# LR1121EVM.net
KiCad netlist of a schematic drawn in Altium Designer
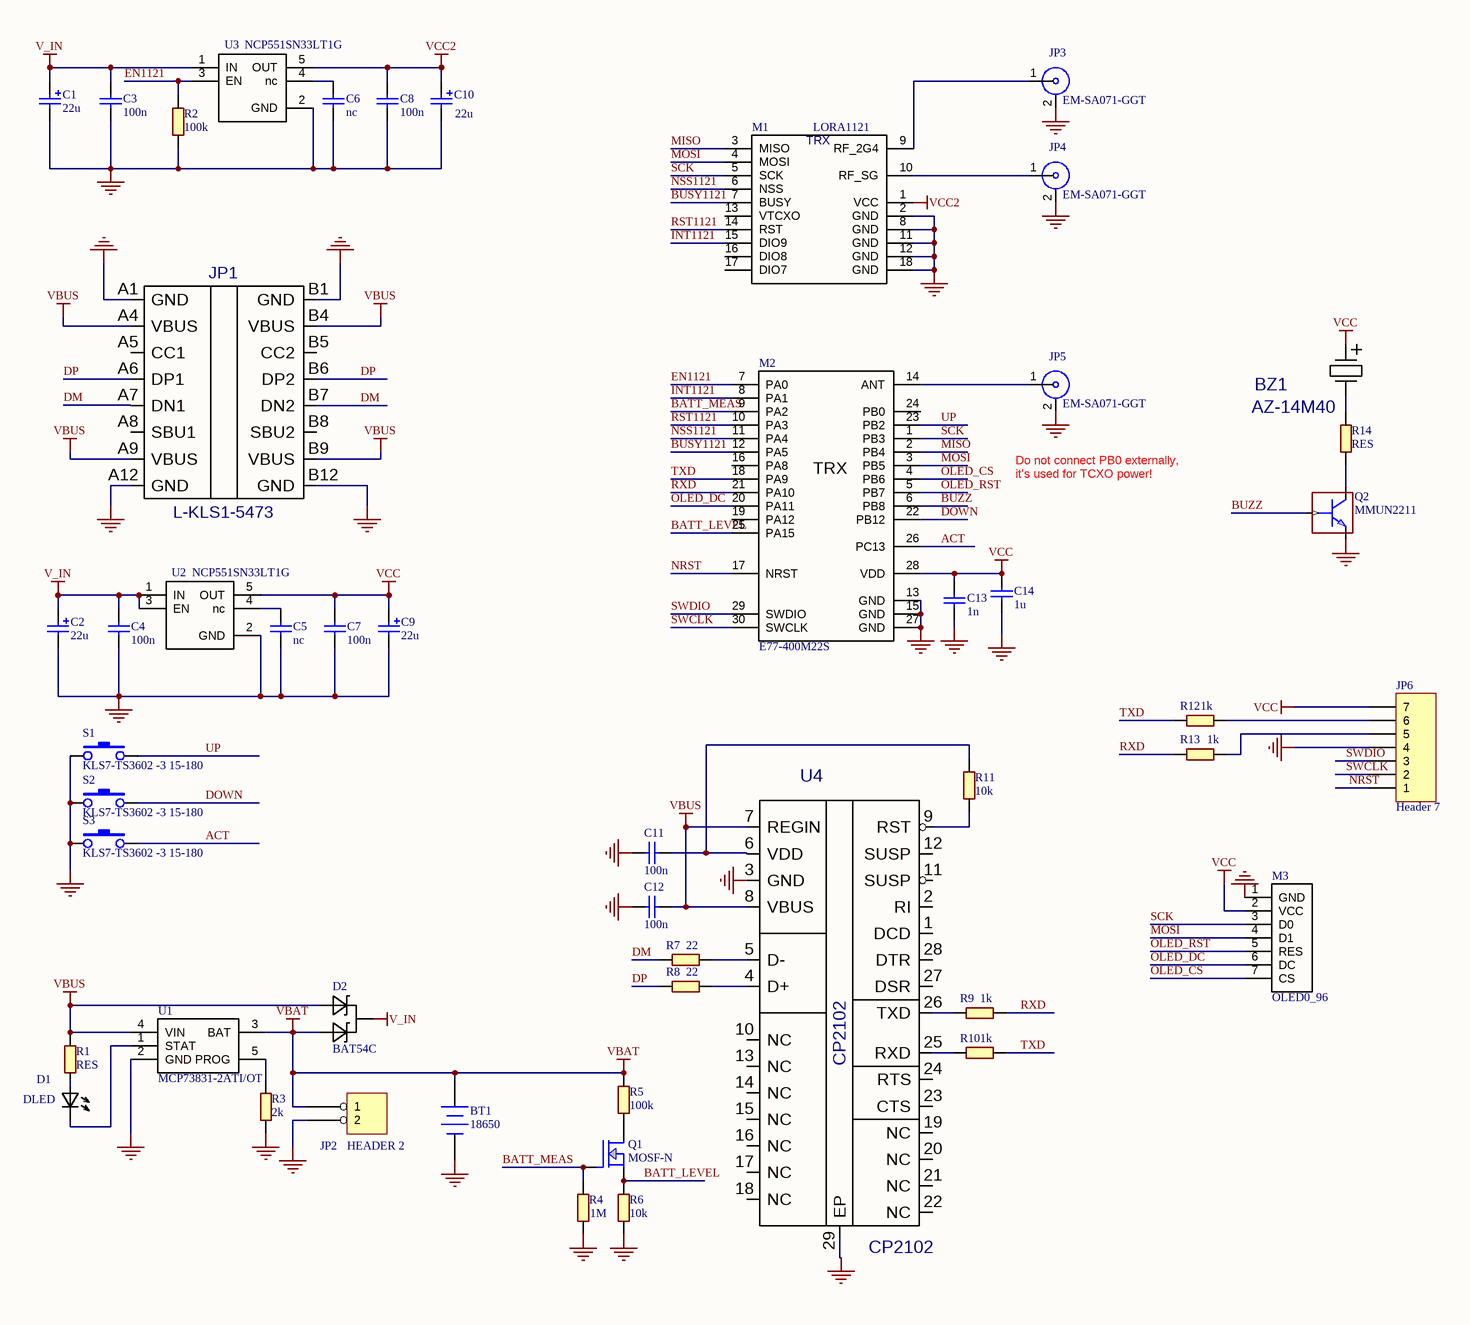
[diagram p0: LR1121EVM.SchDoc]

(export (version "E")
  (design (tool "Eeschema 10.0.6"))
  (components
    (comp (ref "BT1")
      (value "18650")
      (footprint "18650")
      (description "Multicell Battery")
      (fields (field (name "PUBLISHER") "Altium Limited"))
      (libsource (lib "zucker") (part "Battery"))
    )
    (comp (ref "BZ1")
      (value "AZ-14M40")
      (footprint "AZ-14M40")
      (libsource (lib "zucker") (part "BUZ-AZ-14M40"))
    )
    (comp (ref "C1")
      (value "22u")
      (footprint "C_TANTAL_A")
      (fields (field (name "VOLTAGE") "16V"))
      (libsource (lib "Passive") (part "CAPP"))
    )
    (comp (ref "C2")
      (value "22u")
      (footprint "C_TANTAL_A")
      (fields (field (name "VOLTAGE") "16V"))
      (libsource (lib "Passive") (part "CAPP"))
    )
    (comp (ref "C3")
      (value "100n")
      (footprint "C-0603")
      (fields (field (name "VOLTAGE") "50V"))
      (libsource (lib "Passive") (part "CAPN"))
    )
    (comp (ref "C4")
      (value "100n")
      (footprint "C-0603")
      (fields (field (name "VOLTAGE") "50V"))
      (libsource (lib "Passive") (part "CAPN"))
    )
    (comp (ref "C5")
      (value "nc")
      (footprint "C-0603")
      (fields (field (name "VOLTAGE") "50V"))
      (libsource (lib "Passive") (part "CAPN"))
    )
    (comp (ref "C6")
      (value "nc")
      (footprint "C-0603")
      (fields (field (name "VOLTAGE") "50V"))
      (libsource (lib "Passive") (part "CAPN"))
    )
    (comp (ref "C7")
      (value "100n")
      (footprint "C-0603")
      (fields (field (name "VOLTAGE") "50V"))
      (libsource (lib "Passive") (part "CAPN"))
    )
    (comp (ref "C8")
      (value "100n")
      (footprint "C-0603")
      (fields (field (name "VOLTAGE") "50V"))
      (libsource (lib "Passive") (part "CAPN"))
    )
    (comp (ref "C9")
      (value "22u")
      (footprint "C_TANTAL_A")
      (fields (field (name "VOLTAGE") "16V"))
      (libsource (lib "Passive") (part "CAPP"))
    )
    (comp (ref "C10")
      (value "22u")
      (footprint "C_TANTAL_A")
      (fields (field (name "VOLTAGE") "16V"))
      (libsource (lib "Passive") (part "CAPP"))
    )
    (comp (ref "C11")
      (value "100n")
      (footprint "C-0603")
      (fields (field (name "VOLTAGE") "50V"))
      (libsource (lib "Passive") (part "CAPN"))
    )
    (comp (ref "C12")
      (value "100n")
      (footprint "C-0603")
      (fields (field (name "VOLTAGE") "50V"))
      (libsource (lib "Passive") (part "CAPN"))
    )
    (comp (ref "C13")
      (value "1n")
      (footprint "C-0603")
      (fields (field (name "VOLTAGE") "50V"))
      (libsource (lib "Passive") (part "CAPN"))
    )
    (comp (ref "C14")
      (value "1u")
      (footprint "C-0603")
      (fields (field (name "VOLTAGE") "50V"))
      (libsource (lib "Passive") (part "CAPN"))
    )
    (comp (ref "D1") (value "DLED") (footprint "LED_3mm_RED") (libsource (lib "zucker") (part "DLED")))
    (comp (ref "D2") (value "BAT54C") (footprint "SOT-23") (libsource (lib "zucker") (part "BAT54C")))
    (comp (ref "JP1")
      (value "L-KLS1-5473")
      (footprint "L-KLS1-5473")
      (libsource (lib "connectors") (part "L-KLS1-5473"))
    )
    (comp (ref "JP2")
      (value "HEADER 2")
      (footprint "PLS1-2")
      (libsource (lib "Connectors") (part "HEADER 2"))
    )
    (comp (ref "JP3")
      (value "EM-SA071-GGT")
      (footprint "SMA_F_EDGE")
      (description "SMA Female R/A PCB Mount")
      (libsource (lib "Connectors") (part "SMA"))
    )
    (comp (ref "JP4")
      (value "EM-SA071-GGT")
      (footprint "SMA_F_EDGE")
      (description "SMA Female R/A PCB Mount")
      (libsource (lib "Connectors") (part "SMA"))
    )
    (comp (ref "JP5")
      (value "EM-SA071-GGT")
      (footprint "SMA_F_EDGE")
      (description "SMA Female R/A PCB Mount")
      (libsource (lib "Connectors") (part "SMA"))
    )
    (comp (ref "JP6")
      (value "Header 7")
      (footprint "PLS1-7R")
      (description "Header, 7-Pin")
      (fields (field (name "PUBLISHER") "Altium Limited"))
      (libsource (lib "Miscellaneous Connectors") (part "Header 7"))
    )
    (comp (ref "M1")
      (value "LORA1121")
      (footprint "LORA1121")
      (libsource (lib "LR1121EVM") (part "LORA1121"))
    )
    (comp (ref "M2")
      (value "E77-400M22S")
      (footprint "E77XX-M22")
      (libsource (lib "zucker") (part "E77-400M22S"))
    )
    (comp (ref "M3") (value "OLED0_96") (footprint "OLED096") (libsource (lib "zucker") (part "OLED0_96")))
    (comp (ref "Q1") (value "MOSF-N") (footprint "SOT-23") (libsource (lib "Transistors") (part "MOSF-N")))
    (comp (ref "Q2")
      (value "MMUN2211")
      (footprint "SOT-23")
      (libsource (lib "Transistors") (part "MMUN2211"))
    )
    (comp (ref "R1") (value "RES") (footprint "R-0603") (libsource (lib "Passive") (part "RES")))
    (comp (ref "R2") (value "100k") (footprint "R-0603") (libsource (lib "Passive") (part "RES")))
    (comp (ref "R3") (value "2k") (footprint "R-0603") (libsource (lib "") (part "RES_2")))
    (comp (ref "R4") (value "1M") (footprint "R-0603") (libsource (lib "Passive") (part "RES")))
    (comp (ref "R5") (value "100k") (footprint "R-0603") (libsource (lib "Passive") (part "RES")))
    (comp (ref "R6") (value "10k") (footprint "R-0603") (libsource (lib "Passive") (part "RES")))
    (comp (ref "R7") (value "22") (footprint "R-0603") (libsource (lib "") (part "RES_1")))
    (comp (ref "R8") (value "22") (footprint "R-0603") (libsource (lib "") (part "RES_1")))
    (comp (ref "R9") (value "1k") (footprint "R-0603") (libsource (lib "") (part "RES_1")))
    (comp (ref "R10") (value "1k") (footprint "R-0603") (libsource (lib "") (part "RES_1")))
    (comp (ref "R11") (value "10k") (footprint "R-0603") (libsource (lib "Passive") (part "RES")))
    (comp (ref "R12") (value "1k") (footprint "R-0603") (libsource (lib "") (part "RES_1")))
    (comp (ref "R13") (value "1k") (footprint "R-0603") (libsource (lib "") (part "RES_1")))
    (comp (ref "R14") (value "RES") (footprint "R-0603") (libsource (lib "Passive") (part "RES")))
    (comp (ref "S1")
      (value "KLS7-TS3602 -3 15-180")
      (footprint "KLS7-TS3602")
      (libsource (lib "Switches") (part "SW-1"))
    )
    (comp (ref "S2")
      (value "KLS7-TS3602 -3 15-180")
      (footprint "KLS7-TS3602")
      (libsource (lib "Switches") (part "SW-1"))
    )
    (comp (ref "S3")
      (value "KLS7-TS3602 -3 15-180")
      (footprint "KLS7-TS3602")
      (libsource (lib "Switches") (part "SW-1"))
    )
    (comp (ref "U1")
      (value "MCP73831-2ATI/OT")
      (footprint "SOT-23-5")
      (libsource (lib "zucker") (part "MCP73831"))
    )
    (comp (ref "U2")
      (value "NCP551SN33LT1G")
      (footprint "SOT-23-5")
      (description "50mA Low-Dropout Regulator")
      (libsource (lib "zucker") (part "LP2980"))
    )
    (comp (ref "U3")
      (value "NCP551SN33LT1G")
      (footprint "SOT-23-5")
      (description "50mA Low-Dropout Regulator")
      (libsource (lib "zucker") (part "LP2980"))
    )
    (comp (ref "U4") (value "CP2102") (footprint "QFN28") (libsource (lib "E2002") (part "CP2102")))
  )
  (nets
    (net (code "1") (name "/ACT") (class "Default")
      (node (ref "M2") (pin "26") (pinfunction "PC13_26") (pintype "passive"))
      (node (ref "S3") (pin "2") (pinfunction "2_2") (pintype "passive"))
    )
    (net (code "2") (name "/BATT_LEVEL") (class "Default")
      (node (ref "M2") (pin "25") (pinfunction "PA15_25") (pintype "passive"))
      (node (ref "Q1") (pin "2") (pinfunction "SOURCE_2") (pintype "passive"))
      (node (ref "R6") (pin "1") (pinfunction "1_1") (pintype "passive"))
    )
    (net (code "3") (name "/BATT_MEAS") (class "Default")
      (node (ref "M2") (pin "9") (pinfunction "PA2_9") (pintype "passive"))
      (node (ref "Q1") (pin "1") (pinfunction "GATE_1") (pintype "passive"))
      (node (ref "R4") (pin "1") (pinfunction "1_1") (pintype "passive"))
    )
    (net (code "4") (name "/BUSY1121") (class "Default")
      (node (ref "M1") (pin "7") (pinfunction "BUSY_7") (pintype "passive"))
      (node (ref "M2") (pin "12") (pinfunction "PA5_12") (pintype "passive"))
    )
    (net (code "5") (name "/BUZZ") (class "Default")
      (node (ref "M2") (pin "6") (pinfunction "PB8_6") (pintype "passive"))
      (node (ref "Q2") (pin "1") (pinfunction "BASE_1") (pintype "input"))
    )
    (net (code "6") (name "/DM") (class "Default")
      (node (ref "JP1") (pin "A7") (pinfunction "DN1_A7") (pintype "passive"))
      (node (ref "JP1") (pin "B7") (pinfunction "DN2_B7") (pintype "passive"))
      (node (ref "R7") (pin "2") (pinfunction "2_2") (pintype "passive"))
    )
    (net (code "7") (name "/DOWN") (class "Default")
      (node (ref "M2") (pin "22") (pinfunction "PB12_22") (pintype "passive"))
      (node (ref "S2") (pin "2") (pinfunction "2_2") (pintype "passive"))
    )
    (net (code "8") (name "/DP") (class "Default")
      (node (ref "JP1") (pin "A6") (pinfunction "DP1_A6") (pintype "passive"))
      (node (ref "JP1") (pin "B6") (pinfunction "DP2_B6") (pintype "passive"))
      (node (ref "R8") (pin "2") (pinfunction "2_2") (pintype "passive"))
    )
    (net (code "9") (name "/EN1121") (class "Default")
      (node (ref "M2") (pin "7") (pinfunction "PA0_7") (pintype "passive"))
      (node (ref "R2") (pin "1") (pinfunction "1_1") (pintype "passive"))
      (node (ref "U3") (pin "3") (pinfunction "EN_3") (pintype "passive"))
    )
    (net (code "10") (name "/INT1121") (class "Default")
      (node (ref "M1") (pin "15") (pinfunction "DIO9_15") (pintype "passive"))
      (node (ref "M2") (pin "8") (pinfunction "PA1_8") (pintype "passive"))
    )
    (net (code "11") (name "/MISO") (class "Default")
      (node (ref "M1") (pin "3") (pinfunction "MISO_3") (pintype "passive"))
      (node (ref "M2") (pin "2") (pinfunction "PB4_2") (pintype "passive"))
    )
    (net (code "12") (name "/MOSI") (class "Default")
      (node (ref "M1") (pin "4") (pinfunction "MOSI_4") (pintype "passive"))
      (node (ref "M2") (pin "3") (pinfunction "PB5_3") (pintype "passive"))
      (node (ref "M3") (pin "4") (pinfunction "D1_4") (pintype "passive"))
    )
    (net (code "13") (name "/NRST") (class "Default")
      (node (ref "JP6") (pin "1") (pinfunction "1_1") (pintype "passive"))
      (node (ref "M2") (pin "17") (pinfunction "NRST_17") (pintype "passive"))
    )
    (net (code "14") (name "/NSS1121") (class "Default")
      (node (ref "M1") (pin "6") (pinfunction "NSS_6") (pintype "passive"))
      (node (ref "M2") (pin "11") (pinfunction "PA4_11") (pintype "passive"))
    )
    (net (code "15") (name "/OLED_CS") (class "Default")
      (node (ref "M2") (pin "4") (pinfunction "PB6_4") (pintype "passive"))
      (node (ref "M3") (pin "7") (pinfunction "CS_7") (pintype "passive"))
    )
    (net (code "16") (name "/OLED_DC") (class "Default")
      (node (ref "M2") (pin "20") (pinfunction "PA11_20") (pintype "passive"))
      (node (ref "M3") (pin "6") (pinfunction "DC_6") (pintype "passive"))
    )
    (net (code "17") (name "/OLED_RST") (class "Default")
      (node (ref "M2") (pin "5") (pinfunction "PB7_5") (pintype "passive"))
      (node (ref "M3") (pin "5") (pinfunction "RES_5") (pintype "passive"))
    )
    (net (code "18") (name "/RST1121") (class "Default")
      (node (ref "M1") (pin "14") (pinfunction "RST_14") (pintype "passive"))
      (node (ref "M2") (pin "10") (pinfunction "PA3_10") (pintype "passive"))
    )
    (net (code "19") (name "/RXD") (class "Default")
      (node (ref "M2") (pin "21") (pinfunction "PA10_21") (pintype "passive"))
      (node (ref "R13") (pin "2") (pinfunction "2_2") (pintype "passive"))
      (node (ref "R9") (pin "1") (pinfunction "1_1") (pintype "passive"))
    )
    (net (code "20") (name "/SCK") (class "Default")
      (node (ref "M1") (pin "5") (pinfunction "SCK_5") (pintype "passive"))
      (node (ref "M2") (pin "1") (pinfunction "PB3_1") (pintype "passive"))
      (node (ref "M3") (pin "3") (pinfunction "D0_3") (pintype "passive"))
    )
    (net (code "21") (name "/SWCLK") (class "Default")
      (node (ref "JP6") (pin "2") (pinfunction "2_2") (pintype "passive"))
      (node (ref "M2") (pin "30") (pinfunction "SWCLK_30") (pintype "passive"))
    )
    (net (code "22") (name "/SWDIO") (class "Default")
      (node (ref "JP6") (pin "3") (pinfunction "3_3") (pintype "passive"))
      (node (ref "M2") (pin "29") (pinfunction "SWDIO_29") (pintype "passive"))
    )
    (net (code "23") (name "/TXD") (class "Default")
      (node (ref "M2") (pin "18") (pinfunction "PA9_18") (pintype "passive"))
      (node (ref "R10") (pin "1") (pinfunction "1_1") (pintype "passive"))
      (node (ref "R12") (pin "2") (pinfunction "2_2") (pintype "passive"))
    )
    (net (code "24") (name "/UP") (class "Default")
      (node (ref "M2") (pin "23") (pinfunction "PB2_23") (pintype "passive"))
      (node (ref "S1") (pin "2") (pinfunction "2_2") (pintype "passive"))
    )
    (net (code "25") (name "GND") (class "Default")
      (node (ref "BT1") (pin "2") (pinfunction "-_2") (pintype "passive"))
      (node (ref "C1") (pin "1") (pinfunction "1_1") (pintype "passive"))
      (node (ref "C10") (pin "1") (pinfunction "1_1") (pintype "passive"))
      (node (ref "C11") (pin "2") (pinfunction "2_2") (pintype "passive"))
      (node (ref "C12") (pin "1") (pinfunction "1_1") (pintype "passive"))
      (node (ref "C13") (pin "2") (pinfunction "2_2") (pintype "passive"))
      (node (ref "C14") (pin "2") (pinfunction "2_2") (pintype "passive"))
      (node (ref "C2") (pin "1") (pinfunction "1_1") (pintype "passive"))
      (node (ref "C3") (pin "2") (pinfunction "2_2") (pintype "passive"))
      (node (ref "C4") (pin "2") (pinfunction "2_2") (pintype "passive"))
      (node (ref "C5") (pin "2") (pinfunction "2_2") (pintype "passive"))
      (node (ref "C6") (pin "2") (pinfunction "2_2") (pintype "passive"))
      (node (ref "C7") (pin "2") (pinfunction "2_2") (pintype "passive"))
      (node (ref "C8") (pin "2") (pinfunction "2_2") (pintype "passive"))
      (node (ref "C9") (pin "1") (pinfunction "1_1") (pintype "passive"))
      (node (ref "JP1") (pin "A1") (pinfunction "GND_A1") (pintype "passive"))
      (node (ref "JP1") (pin "A12") (pinfunction "GND_A12") (pintype "passive"))
      (node (ref "JP1") (pin "B1") (pinfunction "GND_B1") (pintype "passive"))
      (node (ref "JP1") (pin "B12") (pinfunction "GND_B12") (pintype "passive"))
      (node (ref "JP2") (pin "2") (pinfunction "2_2") (pintype "passive"))
      (node (ref "JP3") (pin "2") (pinfunction "2_2") (pintype "passive"))
      (node (ref "JP4") (pin "2") (pinfunction "2_2") (pintype "passive"))
      (node (ref "JP5") (pin "2") (pinfunction "2_2") (pintype "passive"))
      (node (ref "JP6") (pin "4") (pinfunction "4_4") (pintype "passive"))
      (node (ref "M1") (pin "11") (pinfunction "GND_11") (pintype "passive"))
      (node (ref "M1") (pin "12") (pinfunction "GND_12") (pintype "passive"))
      (node (ref "M1") (pin "18") (pinfunction "GND_18") (pintype "passive"))
      (node (ref "M1") (pin "2") (pinfunction "GND_2") (pintype "passive"))
      (node (ref "M1") (pin "8") (pinfunction "GND_8") (pintype "passive"))
      (node (ref "M2") (pin "13") (pinfunction "GND_13") (pintype "passive"))
      (node (ref "M2") (pin "15") (pinfunction "GND_15") (pintype "passive"))
      (node (ref "M2") (pin "27") (pinfunction "GND_27") (pintype "passive"))
      (node (ref "M3") (pin "1") (pinfunction "GND_1") (pintype "passive"))
      (node (ref "Q2") (pin "2") (pinfunction "EMITTER_2") (pintype "passive"))
      (node (ref "R2") (pin "2") (pinfunction "2_2") (pintype "passive"))
      (node (ref "R3") (pin "1") (pinfunction "1_1") (pintype "passive"))
      (node (ref "R4") (pin "2") (pinfunction "2_2") (pintype "passive"))
      (node (ref "R6") (pin "2") (pinfunction "2_2") (pintype "passive"))
      (node (ref "S1") (pin "1") (pinfunction "1_1") (pintype "passive"))
      (node (ref "S2") (pin "1") (pinfunction "1_1") (pintype "passive"))
      (node (ref "S3") (pin "1") (pinfunction "1_1") (pintype "passive"))
      (node (ref "U1") (pin "2") (pinfunction "GND_2") (pintype "passive"))
      (node (ref "U2") (pin "2") (pinfunction "GND_2") (pintype "passive"))
      (node (ref "U3") (pin "2") (pinfunction "GND_2") (pintype "passive"))
      (node (ref "U4") (pin "29") (pinfunction "EP_29") (pintype "passive"))
      (node (ref "U4") (pin "3") (pinfunction "GND_3") (pintype "passive"))
    )
    (net (code "26") (name "Net-(BZ1-Pad2)") (class "Default")
      (node (ref "BZ1") (pin "2") (pinfunction "2_2") (pintype "passive"))
      (node (ref "R14") (pin "1") (pinfunction "1_1") (pintype "passive"))
    )
    (net (code "27") (name "Net-(D1-Pad1)") (class "Default")
      (node (ref "D1") (pin "1") (pinfunction "1_1") (pintype "passive"))
      (node (ref "R1") (pin "2") (pinfunction "2_2") (pintype "passive"))
    )
    (net (code "28") (name "Net-(JP6-Pad5)") (class "Default")
      (node (ref "JP6") (pin "5") (pinfunction "5_5") (pintype "passive"))
      (node (ref "R13") (pin "1") (pinfunction "1_1") (pintype "passive"))
    )
    (net (code "29") (name "Net-(JP6-Pad6)") (class "Default")
      (node (ref "JP6") (pin "6") (pinfunction "6_6") (pintype "passive"))
      (node (ref "R12") (pin "1") (pinfunction "1_1") (pintype "passive"))
    )
    (net (code "30") (name "Net-(M1-RF_2G4)") (class "Default")
      (node (ref "JP3") (pin "1") (pinfunction "1_1") (pintype "passive"))
      (node (ref "M1") (pin "9") (pinfunction "RF_2G4_9") (pintype "passive"))
    )
    (net (code "31") (name "Net-(M1-RF_SG)") (class "Default")
      (node (ref "JP4") (pin "1") (pinfunction "1_1") (pintype "passive"))
      (node (ref "M1") (pin "10") (pinfunction "RF_SG_10") (pintype "passive"))
    )
    (net (code "32") (name "Net-(M2-ANT)") (class "Default")
      (node (ref "JP5") (pin "1") (pinfunction "1_1") (pintype "passive"))
      (node (ref "M2") (pin "14") (pinfunction "ANT_14") (pintype "passive"))
    )
    (net (code "33") (name "Net-(Q1-DRAIN)") (class "Default")
      (node (ref "Q1") (pin "3") (pinfunction "DRAIN_3") (pintype "passive"))
      (node (ref "R5") (pin "2") (pinfunction "2_2") (pintype "passive"))
    )
    (net (code "34") (name "Net-(Q2-COLLECTOR)") (class "Default")
      (node (ref "Q2") (pin "3") (pinfunction "COLLECTOR_3") (pintype "passive"))
      (node (ref "R14") (pin "2") (pinfunction "2_2") (pintype "passive"))
    )
    (net (code "35") (name "Net-(U1-PROG)") (class "Default")
      (node (ref "R3") (pin "2") (pinfunction "2_2") (pintype "passive"))
      (node (ref "U1") (pin "5") (pinfunction "PROG_5") (pintype "passive"))
    )
    (net (code "36") (name "Net-(U1-STAT)") (class "Default")
      (node (ref "D1") (pin "2") (pinfunction "2_2") (pintype "passive"))
      (node (ref "U1") (pin "1") (pinfunction "STAT_1") (pintype "passive"))
    )
    (net (code "37") (name "Net-(U2-nc)") (class "Default")
      (node (ref "C5") (pin "1") (pinfunction "1_1") (pintype "passive"))
      (node (ref "U2") (pin "4") (pinfunction "nc_4") (pintype "passive"))
    )
    (net (code "38") (name "Net-(U3-nc)") (class "Default")
      (node (ref "C6") (pin "1") (pinfunction "1_1") (pintype "passive"))
      (node (ref "U3") (pin "4") (pinfunction "nc_4") (pintype "passive"))
    )
    (net (code "39") (name "Net-(U4-D+)") (class "Default")
      (node (ref "R8") (pin "1") (pinfunction "1_1") (pintype "passive"))
      (node (ref "U4") (pin "4") (pinfunction "D+_4") (pintype "passive"))
    )
    (net (code "40") (name "Net-(U4-D-)") (class "Default")
      (node (ref "R7") (pin "1") (pinfunction "1_1") (pintype "passive"))
      (node (ref "U4") (pin "5") (pinfunction "D-_5") (pintype "passive"))
    )
    (net (code "41") (name "Net-(U4-RST)") (class "Default")
      (node (ref "R11") (pin "2") (pinfunction "2_2") (pintype "passive"))
      (node (ref "U4") (pin "9") (pinfunction "RST_9") (pintype "passive"))
    )
    (net (code "42") (name "Net-(U4-RXD)") (class "Default")
      (node (ref "R10") (pin "2") (pinfunction "2_2") (pintype "passive"))
      (node (ref "U4") (pin "25") (pinfunction "RXD_25") (pintype "passive"))
    )
    (net (code "43") (name "Net-(U4-TXD)") (class "Default")
      (node (ref "R9") (pin "2") (pinfunction "2_2") (pintype "passive"))
      (node (ref "U4") (pin "26") (pinfunction "TXD_26") (pintype "passive"))
    )
    (net (code "44") (name "Net-(U4-VDD)") (class "Default")
      (node (ref "C11") (pin "1") (pinfunction "1_1") (pintype "passive"))
      (node (ref "R11") (pin "1") (pinfunction "1_1") (pintype "passive"))
      (node (ref "U4") (pin "6") (pinfunction "VDD_6") (pintype "passive"))
    )
    (net (code "45") (name "VBAT") (class "Default")
      (node (ref "BT1") (pin "1") (pinfunction "+_1") (pintype "passive"))
      (node (ref "D2") (pin "1") (pinfunction "A1_1") (pintype "passive"))
      (node (ref "JP2") (pin "1") (pinfunction "1_1") (pintype "passive"))
      (node (ref "R5") (pin "1") (pinfunction "1_1") (pintype "passive"))
      (node (ref "U1") (pin "3") (pinfunction "BAT_3") (pintype "passive"))
    )
    (net (code "46") (name "VBUS") (class "Default")
      (node (ref "C12") (pin "2") (pinfunction "2_2") (pintype "passive"))
      (node (ref "D2") (pin "2") (pinfunction "A2_2") (pintype "passive"))
      (node (ref "JP1") (pin "A4") (pinfunction "VBUS_A4") (pintype "passive"))
      (node (ref "JP1") (pin "A9") (pinfunction "VBUS_A9") (pintype "passive"))
      (node (ref "JP1") (pin "B4") (pinfunction "VBUS_B4") (pintype "passive"))
      (node (ref "JP1") (pin "B9") (pinfunction "VBUS_B9") (pintype "passive"))
      (node (ref "R1") (pin "1") (pinfunction "1_1") (pintype "passive"))
      (node (ref "U1") (pin "4") (pinfunction "VIN_4") (pintype "passive"))
      (node (ref "U4") (pin "7") (pinfunction "REGIN_7") (pintype "passive"))
      (node (ref "U4") (pin "8") (pinfunction "VBUS_8") (pintype "passive"))
    )
    (net (code "47") (name "VCC") (class "Default")
      (node (ref "BZ1") (pin "1") (pinfunction "1_1") (pintype "passive"))
      (node (ref "C13") (pin "1") (pinfunction "1_1") (pintype "passive"))
      (node (ref "C14") (pin "1") (pinfunction "1_1") (pintype "passive"))
      (node (ref "C7") (pin "1") (pinfunction "1_1") (pintype "passive"))
      (node (ref "C9") (pin "2") (pinfunction "2_2") (pintype "passive"))
      (node (ref "JP6") (pin "7") (pinfunction "7_7") (pintype "passive"))
      (node (ref "M2") (pin "28") (pinfunction "VDD_28") (pintype "passive"))
      (node (ref "M3") (pin "2") (pinfunction "VCC_2") (pintype "passive"))
      (node (ref "U2") (pin "5") (pinfunction "OUT_5") (pintype "passive"))
    )
    (net (code "48") (name "VCC2") (class "Default")
      (node (ref "C10") (pin "2") (pinfunction "2_2") (pintype "passive"))
      (node (ref "C8") (pin "1") (pinfunction "1_1") (pintype "passive"))
      (node (ref "M1") (pin "1") (pinfunction "VCC_1") (pintype "passive"))
      (node (ref "U3") (pin "5") (pinfunction "OUT_5") (pintype "passive"))
    )
    (net (code "49") (name "VSS") (class "Default")
      (node (ref "JP1") (pin "17") (pinfunction "VSS_17") (pintype "power_in"))
    )
    (net (code "50") (name "V_IN") (class "Default")
      (node (ref "C1") (pin "2") (pinfunction "2_2") (pintype "passive"))
      (node (ref "C2") (pin "2") (pinfunction "2_2") (pintype "passive"))
      (node (ref "C3") (pin "1") (pinfunction "1_1") (pintype "passive"))
      (node (ref "C4") (pin "1") (pinfunction "1_1") (pintype "passive"))
      (node (ref "D2") (pin "3") (pinfunction "C1C2_3") (pintype "passive"))
      (node (ref "U2") (pin "1") (pinfunction "IN_1") (pintype "passive"))
      (node (ref "U2") (pin "3") (pinfunction "EN_3") (pintype "passive"))
      (node (ref "U3") (pin "1") (pinfunction "IN_1") (pintype "passive"))
    )
    (net (code "51") (name "unconnected-(JP1-CC1-PadA5)") (class "Default")
      (node (ref "JP1") (pin "A5") (pinfunction "CC1_A5") (pintype "passive"))
    )
    (net (code "52") (name "unconnected-(JP1-CC2-PadB5)") (class "Default")
      (node (ref "JP1") (pin "B5") (pinfunction "CC2_B5") (pintype "passive"))
    )
    (net (code "53") (name "unconnected-(JP1-SBU1-PadA8)") (class "Default")
      (node (ref "JP1") (pin "A8") (pinfunction "SBU1_A8") (pintype "passive"))
    )
    (net (code "54") (name "unconnected-(JP1-SBU2-PadB8)") (class "Default")
      (node (ref "JP1") (pin "B8") (pinfunction "SBU2_B8") (pintype "passive"))
    )
    (net (code "55") (name "unconnected-(M1-DIO7-Pad17)") (class "Default")
      (node (ref "M1") (pin "17") (pinfunction "DIO7_17") (pintype "passive"))
    )
    (net (code "56") (name "unconnected-(M1-DIO8-Pad16)") (class "Default")
      (node (ref "M1") (pin "16") (pinfunction "DIO8_16") (pintype "passive"))
    )
    (net (code "57") (name "unconnected-(M1-VTCXO-Pad13)") (class "Default")
      (node (ref "M1") (pin "13") (pinfunction "VTCXO_13") (pintype "passive"))
    )
    (net (code "58") (name "unconnected-(M2-PA8-Pad16)") (class "Default")
      (node (ref "M2") (pin "16") (pinfunction "PA8_16") (pintype "passive"))
    )
    (net (code "59") (name "unconnected-(M2-PA12-Pad19)") (class "Default")
      (node (ref "M2") (pin "19") (pinfunction "PA12_19") (pintype "passive"))
    )
    (net (code "60") (name "unconnected-(M2-PB0-Pad24)") (class "Default")
      (node (ref "M2") (pin "24") (pinfunction "PB0_24") (pintype "passive"))
    )
    (net (code "61") (name "unconnected-(U4-CTS-Pad23)") (class "Default")
      (node (ref "U4") (pin "23") (pinfunction "CTS_23") (pintype "passive"))
    )
    (net (code "62") (name "unconnected-(U4-DCD-Pad1)") (class "Default")
      (node (ref "U4") (pin "1") (pinfunction "DCD_1") (pintype "passive"))
    )
    (net (code "63") (name "unconnected-(U4-DSR-Pad27)") (class "Default")
      (node (ref "U4") (pin "27") (pinfunction "DSR_27") (pintype "passive"))
    )
    (net (code "64") (name "unconnected-(U4-DTR-Pad28)") (class "Default")
      (node (ref "U4") (pin "28") (pinfunction "DTR_28") (pintype "passive"))
    )
    (net (code "65") (name "unconnected-(U4-NC-Pad10)") (class "Default")
      (node (ref "U4") (pin "10") (pinfunction "NC_10") (pintype "passive"))
    )
    (net (code "66") (name "unconnected-(U4-NC-Pad13)") (class "Default")
      (node (ref "U4") (pin "13") (pinfunction "NC_13") (pintype "passive"))
    )
    (net (code "67") (name "unconnected-(U4-NC-Pad14)") (class "Default")
      (node (ref "U4") (pin "14") (pinfunction "NC_14") (pintype "passive"))
    )
    (net (code "68") (name "unconnected-(U4-NC-Pad15)") (class "Default")
      (node (ref "U4") (pin "15") (pinfunction "NC_15") (pintype "passive"))
    )
    (net (code "69") (name "unconnected-(U4-NC-Pad16)") (class "Default")
      (node (ref "U4") (pin "16") (pinfunction "NC_16") (pintype "passive"))
    )
    (net (code "70") (name "unconnected-(U4-NC-Pad17)") (class "Default")
      (node (ref "U4") (pin "17") (pinfunction "NC_17") (pintype "passive"))
    )
    (net (code "71") (name "unconnected-(U4-NC-Pad18)") (class "Default")
      (node (ref "U4") (pin "18") (pinfunction "NC_18") (pintype "passive"))
    )
    (net (code "72") (name "unconnected-(U4-NC-Pad19)") (class "Default")
      (node (ref "U4") (pin "19") (pinfunction "NC_19") (pintype "passive"))
    )
    (net (code "73") (name "unconnected-(U4-NC-Pad20)") (class "Default")
      (node (ref "U4") (pin "20") (pinfunction "NC_20") (pintype "passive"))
    )
    (net (code "74") (name "unconnected-(U4-NC-Pad21)") (class "Default")
      (node (ref "U4") (pin "21") (pinfunction "NC_21") (pintype "passive"))
    )
    (net (code "75") (name "unconnected-(U4-NC-Pad22)") (class "Default")
      (node (ref "U4") (pin "22") (pinfunction "NC_22") (pintype "passive"))
    )
    (net (code "76") (name "unconnected-(U4-RI-Pad2)") (class "Default")
      (node (ref "U4") (pin "2") (pinfunction "RI_2") (pintype "passive"))
    )
    (net (code "77") (name "unconnected-(U4-RTS-Pad24)") (class "Default")
      (node (ref "U4") (pin "24") (pinfunction "RTS_24") (pintype "passive"))
    )
    (net (code "78") (name "unconnected-(U4-SUSP-Pad11)") (class "Default")
      (node (ref "U4") (pin "11") (pinfunction "SUSP_11") (pintype "passive"))
    )
    (net (code "79") (name "unconnected-(U4-SUSP-Pad12)") (class "Default")
      (node (ref "U4") (pin "12") (pinfunction "SUSP_12") (pintype "passive"))
    )
  )
)
